# Soft_Start.net
KiCad netlist of a schematic drawn in Altium Designer
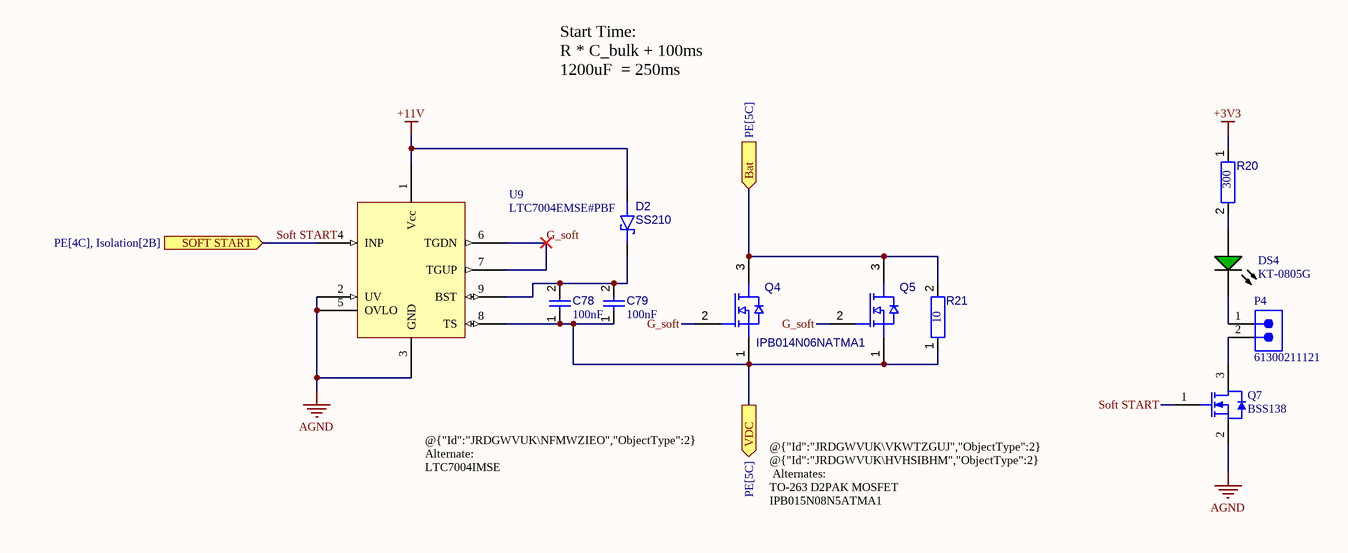
[diagram p0: Soft_Start.SchDoc]

(export (version "E")
  (design (tool "Eeschema 10.0.6"))
  (components
    (comp (ref "C78")
      (value "100nF")
      (footprint "CAPC3216X06N")
      (description "Ceramic Capacitor, Multilayer, Ceramic, 200V, 10% +Tol, 10% -Tol, X7R, 15% TC, 0.01uF, 1206")
      (fields (field (name "TOLERANCE") "10%") (field (name "Comment") "C1206C104K1RACTU"))
      (libsource (lib "University of Galway") (part "CAP-NP-2"))
    )
    (comp (ref "C79")
      (value "100nF")
      (footprint "CAPC3216X06N")
      (description "Ceramic Capacitor, Multilayer, Ceramic, 200V, 10% +Tol, 10% -Tol, X7R, 15% TC, 0.01uF, 1206")
      (fields (field (name "TOLERANCE") "10%") (field (name "Comment") "C1206C104K1RACTU"))
      (libsource (lib "University of Galway") (part "CAP-NP-2"))
    )
    (comp (ref "D2")
      (value "SS210")
      (footprint "DIOM4226X24N")
      (description "Rectifier Diode, Schottky, 1 Phase, 1 Element, 2A, 100V V(RRM), Silicon, DO-214AA")
      (libsource (lib "University of Galway") (part "DIODE-SKY-2"))
    )
    (comp (ref "DS4")
      (value "KT-0805G")
      (footprint "WL-SMCW_0805_150080xx75000")
      (libsource (lib "University of Galway") (part "LED-GREEN-AK-2"))
    )
    (comp (ref "P4")
      (value "61300211121")
      (footprint "61300211121")
      (description "WR-PHD Pin Header, THT, Vertical, pitch 2.54mm, 1 Row, 2P")
      (fields (field (name "MANUFACTURER") "Wurth Elektronik"))
      (libsource (lib "University of Galway") (part "62000211121"))
    )
    (comp (ref "Q4")
      (value "IPB014N06NATMA1")
      (footprint "INF-PG-TO263-7-1_M")
      (description "Power MOSFET, N Channel, 60 V, 180 A, 0.0012 ohm, TO-263 (D2PAK), Surface Mount")
      (libsource (lib "University of Galway") (part "CMP-00089-6"))
    )
    (comp (ref "Q5")
      (value "IPB014N06NATMA1")
      (footprint "INF-PG-TO263-7-1_M")
      (description "Power MOSFET, N Channel, 60 V, 180 A, 0.0012 ohm, TO-263 (D2PAK), Surface Mount")
      (libsource (lib "University of Galway") (part "CMP-00089-6"))
    )
    (comp (ref "Q7")
      (value "BSS138")
      (footprint "FAIR-SOT23-3_V")
      (fields (field (name "MANUFACTURER") "Fairchild") (field (name "POWER") "360mW"))
      (libsource (lib "University of Galway") (part "NEMOS-GSD-3"))
    )
    (comp (ref "R20")
      (value "300")
      (footprint "RESC3216X89X51NL25T25")
      (description "250mW Thick Film Resistors 200V ±100ppm/℃ ±1% 300Ω 1206 Chip Resistor - Surface Mount ROHS")
      (fields (field (name "Comment") "1206W4F3000T5E"))
      (libsource (lib "University of Galway") (part "RES-2"))
    )
    (comp (ref "R21")
      (value "10")
      (footprint "1623730-2-Footprint-1")
      (description "Fixed Resistor, Wire Wound, 4W, 10ohm, 6.3246V, 5% +/-Tol, 400ppm/Cel, Through Hole Mount, 3228")
      (fields (field (name "TOLERANCE") "5%") (field (name "Comment") "1623730-2"))
      (libsource (lib "University of Galway") (part "RES-2"))
    )
    (comp (ref "U9")
      (value "LTC7004EMSE#PBF")
      (footprint "TSSOP50P490X110_HS-11N")
      (description "RoHS Compliant PRODUCTION (Last Updated: 2weeks ago) MSOP IC Gate Driver")
      (libsource (lib "University of Galway") (part "LTC7004EMSE#PBF"))
    )
  )
  (nets
    (net (code "1") (name "+3V3") (class "Default")
      (node (ref "R20") (pin "1") (pinfunction "1_1") (pintype "passive"))
    )
    (net (code "2") (name "+11V") (class "Default")
      (node (ref "D2") (pin "2") (pinfunction "A_2") (pintype "passive"))
      (node (ref "U9") (pin "1") (pinfunction "Vcc_1") (pintype "power_in"))
    )
    (net (code "3") (name "/Bat") (class "Default")
      (node (ref "Q4") (pin "3") (pinfunction "D_3") (pintype "passive"))
      (node (ref "Q5") (pin "3") (pinfunction "D_3") (pintype "passive"))
      (node (ref "R21") (pin "2") (pinfunction "2_2") (pintype "passive"))
    )
    (net (code "4") (name "/G_soft") (class "Default")
      (node (ref "Q4") (pin "2") (pinfunction "G_2") (pintype "passive"))
      (node (ref "Q5") (pin "2") (pinfunction "G_2") (pintype "passive"))
      (node (ref "U9") (pin "6") (pinfunction "TGDN_6") (pintype "output"))
      (node (ref "U9") (pin "7") (pinfunction "TGUP_7") (pintype "output"))
    )
    (net (code "5") (name "/Soft START") (class "Default")
      (node (ref "Q7") (pin "1") (pinfunction "G_1") (pintype "passive"))
      (node (ref "U9") (pin "4") (pinfunction "INP_4") (pintype "input"))
    )
    (net (code "6") (name "/VDC") (class "Default")
      (node (ref "C78") (pin "1") (pinfunction "1_1") (pintype "passive"))
      (node (ref "C79") (pin "1") (pinfunction "1_1") (pintype "passive"))
      (node (ref "Q4") (pin "1") (pinfunction "S_1") (pintype "passive"))
      (node (ref "Q5") (pin "1") (pinfunction "S_1") (pintype "passive"))
      (node (ref "R21") (pin "1") (pinfunction "1_1") (pintype "passive"))
      (node (ref "U9") (pin "8") (pinfunction "TS_8") (pintype "bidirectional"))
    )
    (net (code "7") (name "AGND") (class "Default")
      (node (ref "Q7") (pin "2") (pinfunction "S_2") (pintype "passive"))
      (node (ref "U9") (pin "2") (pinfunction "UV_2") (pintype "input"))
      (node (ref "U9") (pin "3") (pinfunction "GND_3") (pintype "power_in"))
      (node (ref "U9") (pin "5") (pinfunction "OVLO_5") (pintype "passive"))
    )
    (net (code "8") (name "Net-(D2-K)") (class "Default")
      (node (ref "C78") (pin "2") (pinfunction "2_2") (pintype "passive"))
      (node (ref "C79") (pin "2") (pinfunction "2_2") (pintype "passive"))
      (node (ref "D2") (pin "1") (pinfunction "K_1") (pintype "passive"))
      (node (ref "U9") (pin "9") (pinfunction "BST_9") (pintype "bidirectional"))
    )
    (net (code "9") (name "Net-(DS4-A)") (class "Default")
      (node (ref "DS4") (pin "1") (pinfunction "A_1") (pintype "passive"))
      (node (ref "R20") (pin "2") (pinfunction "2_2") (pintype "passive"))
    )
    (net (code "10") (name "Net-(DS4-K)") (class "Default")
      (node (ref "DS4") (pin "2") (pinfunction "K_2") (pintype "passive"))
      (node (ref "P4") (pin "1") (pinfunction "1_1") (pintype "passive"))
    )
    (net (code "11") (name "Net-(Q7-D)") (class "Default")
      (node (ref "P4") (pin "2") (pinfunction "2_2") (pintype "passive"))
      (node (ref "Q7") (pin "3") (pinfunction "D_3") (pintype "passive"))
    )
  )
)
